# Christmas_Tree_V2.net
KiCad netlist of a schematic drawn in EasyEDA
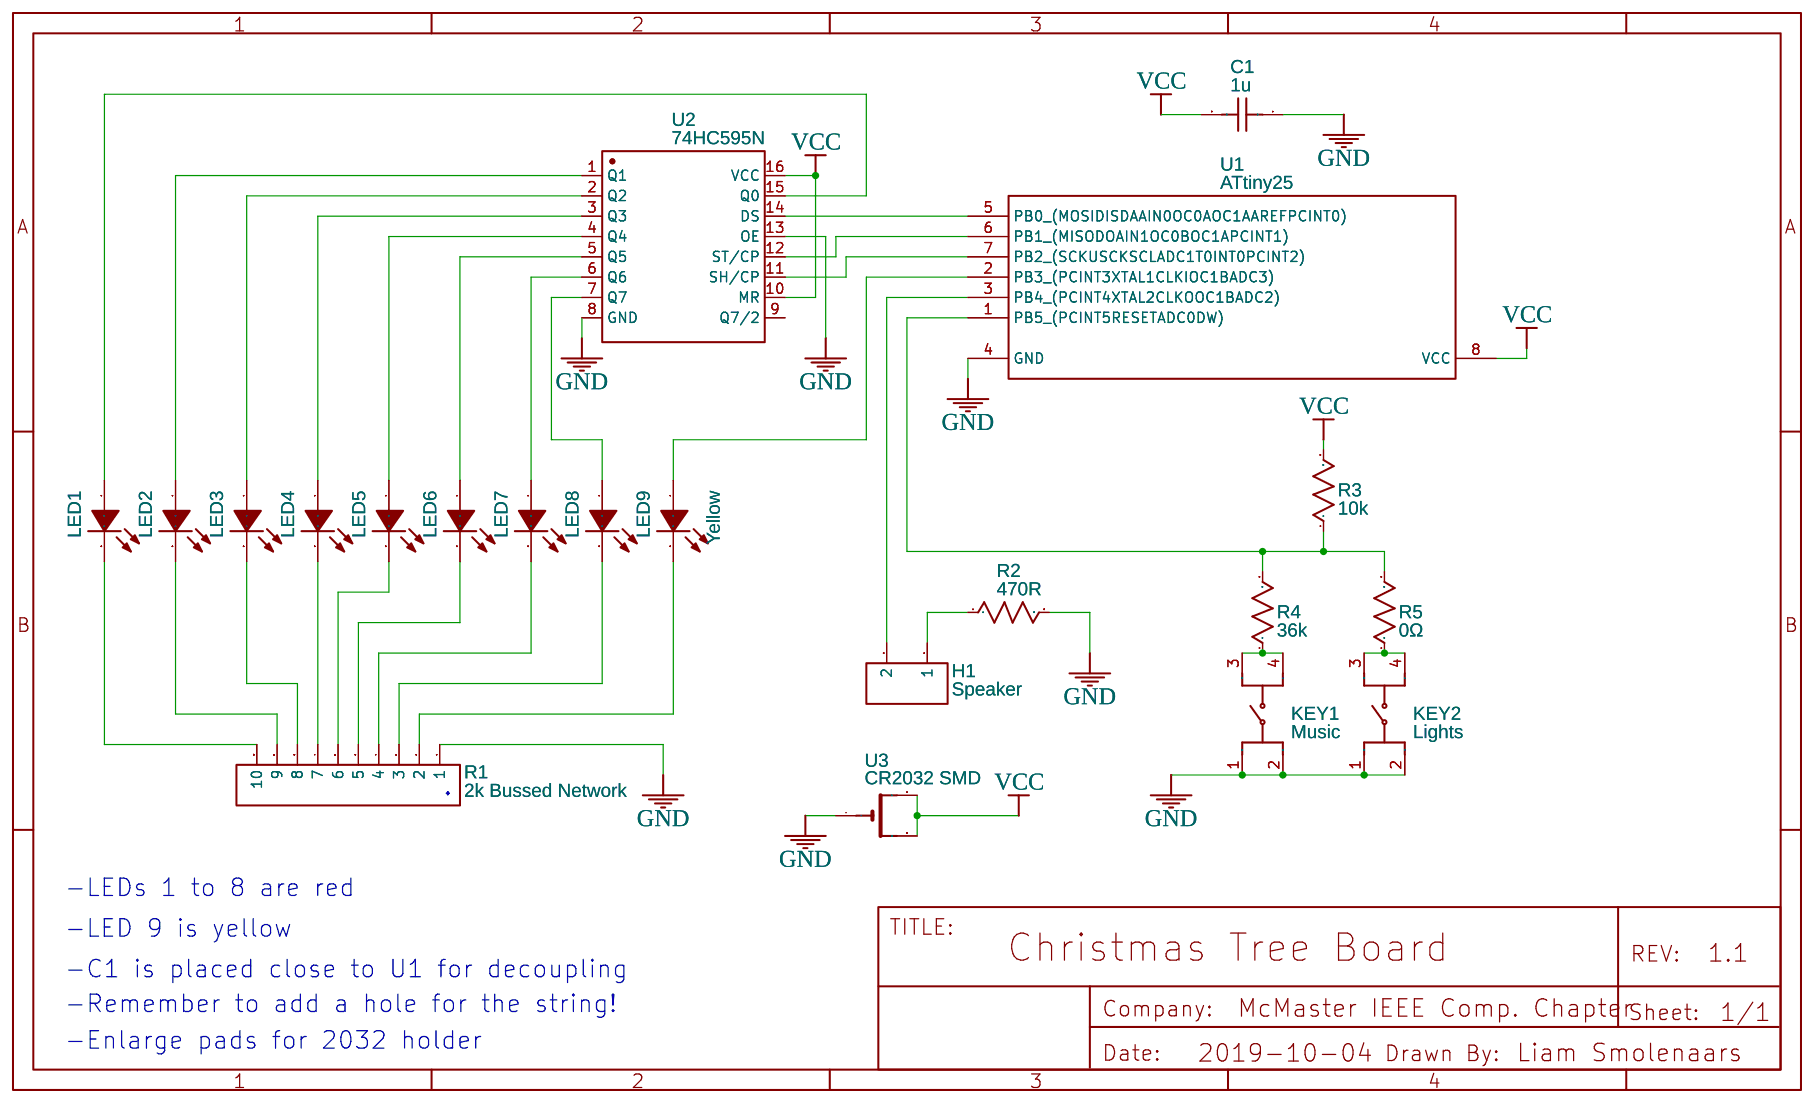
[diagram p0: schematic sheet]

(export (version "E")
  (design (tool "Eeschema 10.0.6"))
  (components
    (comp (ref "C1") (value "1u") (libsource (lib "") (part "Cap_RAD-0.1_US")))
    (comp (ref "H1")
      (value "Speaker")
      (fields (field (name "BOM_Manufacturer Part") "826629-2") (field (name "BOM_Supplier Part") "C86471"))
      (libsource (lib "") (part "Unknown_440_325"))
    )
    (comp (ref "KEY1")
      (value "Music")
      (fields
        (field (name "BOM_Manufacturer Part") "TS-1102-5016")
        (field (name "BOM_Supplier Part") "C111609")
      )
      (libsource (lib "") (part "Unknown_610_345"))
    )
    (comp (ref "KEY2")
      (value "Lights")
      (fields
        (field (name "BOM_Manufacturer Part") "TS-1102-5016")
        (field (name "BOM_Supplier Part") "C111609")
      )
      (libsource (lib "") (part "Unknown_670_345"))
    )
    (comp (ref "LED1")
      (value "204-10SURD/S530-A3")
      (fields (field (name "BOM_Supplier Part") "C99772"))
      (libsource (lib "") (part "Unknown_50_250"))
    )
    (comp (ref "LED2")
      (value "204-10SURD/S530-A3")
      (fields (field (name "BOM_Supplier Part") "C99772"))
      (libsource (lib "") (part "Unknown_85_250"))
    )
    (comp (ref "LED3")
      (value "204-10SURD/S530-A3")
      (fields (field (name "BOM_Supplier Part") "C99772"))
      (libsource (lib "") (part "Unknown_120_250"))
    )
    (comp (ref "LED4")
      (value "204-10SURD/S530-A3")
      (fields (field (name "BOM_Supplier Part") "C99772"))
      (libsource (lib "") (part "Unknown_155_250"))
    )
    (comp (ref "LED5")
      (value "204-10SURD/S530-A3")
      (fields (field (name "BOM_Supplier Part") "C99772"))
      (libsource (lib "") (part "Unknown_190_250"))
    )
    (comp (ref "LED6")
      (value "204-10SURD/S530-A3")
      (fields (field (name "BOM_Supplier Part") "C99772"))
      (libsource (lib "") (part "Unknown_225_250"))
    )
    (comp (ref "LED7")
      (value "204-10SURD/S530-A3")
      (fields (field (name "BOM_Supplier Part") "C99772"))
      (libsource (lib "") (part "Unknown_260_250"))
    )
    (comp (ref "LED8")
      (value "204-10SURD/S530-A3")
      (fields (field (name "BOM_Supplier Part") "C99772"))
      (libsource (lib "") (part "Unknown_295_250"))
    )
    (comp (ref "LED9")
      (value "Yellow")
      (fields
        (field (name "BOM_Manufacturer Part") "204-10SURD/S530-A3")
        (field (name "BOM_Supplier Part") "C99772")
      )
      (libsource (lib "") (part "Unknown_330_250"))
    )
    (comp (ref "R1")
      (value "2k Bussed Network")
      (fields
        (field (name "BOM_Manufacturer Part") "2.54mm 1*10P Straight Female header Gold-plated")
        (field (name "BOM_Supplier Part") "C35445")
      )
      (libsource (lib "") (part "Unknown_160_370"))
    )
    (comp (ref "R2") (value "470R") (libsource (lib "") (part "Res_0805(1/8W)_US_1")))
    (comp (ref "R3") (value "10k") (libsource (lib "") (part "Res_0805(1/8W)_US")))
    (comp (ref "R4") (value "36k") (libsource (lib "") (part "Res_0805(1/8W)_US")))
    (comp (ref "R5") (value "0Ω") (libsource (lib "") (part "Res_0805(1/8W)_US")))
    (comp (ref "U1") (value "ATtiny25") (libsource (lib "") (part "Unknown_600_135")))
    (comp (ref "U2") (value "74HC595N") (libsource (lib "") (part "Unknown_330_115")))
    (comp (ref "U3") (value "CR2032 SMD") (libsource (lib "") (part "Unknown_425_395")))
  )
  (nets
    (net (code "1") (name "GND") (class "Default")
      (node (ref "C1") (pin "1") (pinfunction "1_1") (pintype "unspecified"))
      (node (ref "KEY1") (pin "1") (pinfunction "1_1") (pintype "unspecified"))
      (node (ref "KEY1") (pin "2") (pinfunction "2_2") (pintype "unspecified"))
      (node (ref "KEY2") (pin "1") (pinfunction "1_1") (pintype "unspecified"))
      (node (ref "KEY2") (pin "2") (pinfunction "2_2") (pintype "unspecified"))
      (node (ref "R1") (pin "1") (pinfunction "1_1") (pintype "input"))
      (node (ref "R2") (pin "2") (pinfunction "2_2") (pintype "unspecified"))
      (node (ref "U1") (pin "4") (pinfunction "GND_4") (pintype "passive"))
      (node (ref "U2") (pin "13") (pinfunction "OE_13") (pintype "unspecified"))
      (node (ref "U2") (pin "8") (pinfunction "GND_8") (pintype "unspecified"))
      (node (ref "U3") (pin "-") (pinfunction "-_-") (pintype "unspecified"))
    )
    (net (code "2") (name "Net-(H1-Pad1)") (class "Default")
      (node (ref "H1") (pin "1") (pinfunction "1_1") (pintype "unspecified"))
      (node (ref "R2") (pin "1") (pinfunction "1_1") (pintype "unspecified"))
    )
    (net (code "3") (name "Net-(KEY1-Pad3)") (class "Default")
      (node (ref "KEY1") (pin "3") (pinfunction "3_3") (pintype "unspecified"))
      (node (ref "KEY1") (pin "4") (pinfunction "4_4") (pintype "unspecified"))
      (node (ref "R4") (pin "1") (pinfunction "1_1") (pintype "unspecified"))
    )
    (net (code "4") (name "Net-(KEY2-Pad3)") (class "Default")
      (node (ref "KEY2") (pin "3") (pinfunction "3_3") (pintype "unspecified"))
      (node (ref "KEY2") (pin "4") (pinfunction "4_4") (pintype "unspecified"))
      (node (ref "R5") (pin "1") (pinfunction "1_1") (pintype "unspecified"))
    )
    (net (code "5") (name "Net-(LED1-A)") (class "Default")
      (node (ref "LED1") (pin "1") (pinfunction "A_1") (pintype "unspecified"))
      (node (ref "U2") (pin "15") (pinfunction "Q0_15") (pintype "unspecified"))
    )
    (net (code "6") (name "Net-(LED1-K)") (class "Default")
      (node (ref "LED1") (pin "2") (pinfunction "K_2") (pintype "unspecified"))
      (node (ref "R1") (pin "10") (pinfunction "10_10") (pintype "input"))
    )
    (net (code "7") (name "Net-(LED2-A)") (class "Default")
      (node (ref "LED2") (pin "1") (pinfunction "A_1") (pintype "unspecified"))
      (node (ref "U2") (pin "1") (pinfunction "Q1_1") (pintype "unspecified"))
    )
    (net (code "8") (name "Net-(LED2-K)") (class "Default")
      (node (ref "LED2") (pin "2") (pinfunction "K_2") (pintype "unspecified"))
      (node (ref "R1") (pin "9") (pinfunction "9_9") (pintype "input"))
    )
    (net (code "9") (name "Net-(LED3-A)") (class "Default")
      (node (ref "LED3") (pin "1") (pinfunction "A_1") (pintype "unspecified"))
      (node (ref "U2") (pin "2") (pinfunction "Q2_2") (pintype "unspecified"))
    )
    (net (code "10") (name "Net-(LED3-K)") (class "Default")
      (node (ref "LED3") (pin "2") (pinfunction "K_2") (pintype "unspecified"))
      (node (ref "R1") (pin "8") (pinfunction "8_8") (pintype "input"))
    )
    (net (code "11") (name "Net-(LED4-A)") (class "Default")
      (node (ref "LED4") (pin "1") (pinfunction "A_1") (pintype "unspecified"))
      (node (ref "U2") (pin "3") (pinfunction "Q3_3") (pintype "unspecified"))
    )
    (net (code "12") (name "Net-(LED4-K)") (class "Default")
      (node (ref "LED4") (pin "2") (pinfunction "K_2") (pintype "unspecified"))
      (node (ref "R1") (pin "7") (pinfunction "7_7") (pintype "input"))
    )
    (net (code "13") (name "Net-(LED5-A)") (class "Default")
      (node (ref "LED5") (pin "1") (pinfunction "A_1") (pintype "unspecified"))
      (node (ref "U2") (pin "4") (pinfunction "Q4_4") (pintype "unspecified"))
    )
    (net (code "14") (name "Net-(LED5-K)") (class "Default")
      (node (ref "LED5") (pin "2") (pinfunction "K_2") (pintype "unspecified"))
      (node (ref "R1") (pin "6") (pinfunction "6_6") (pintype "input"))
    )
    (net (code "15") (name "Net-(LED6-A)") (class "Default")
      (node (ref "LED6") (pin "1") (pinfunction "A_1") (pintype "unspecified"))
      (node (ref "U2") (pin "5") (pinfunction "Q5_5") (pintype "unspecified"))
    )
    (net (code "16") (name "Net-(LED6-K)") (class "Default")
      (node (ref "LED6") (pin "2") (pinfunction "K_2") (pintype "unspecified"))
      (node (ref "R1") (pin "5") (pinfunction "5_5") (pintype "input"))
    )
    (net (code "17") (name "Net-(LED7-A)") (class "Default")
      (node (ref "LED7") (pin "1") (pinfunction "A_1") (pintype "unspecified"))
      (node (ref "U2") (pin "6") (pinfunction "Q6_6") (pintype "unspecified"))
    )
    (net (code "18") (name "Net-(LED7-K)") (class "Default")
      (node (ref "LED7") (pin "2") (pinfunction "K_2") (pintype "unspecified"))
      (node (ref "R1") (pin "4") (pinfunction "4_4") (pintype "input"))
    )
    (net (code "19") (name "Net-(LED8-A)") (class "Default")
      (node (ref "LED8") (pin "1") (pinfunction "A_1") (pintype "unspecified"))
      (node (ref "U2") (pin "7") (pinfunction "Q7_7") (pintype "unspecified"))
    )
    (net (code "20") (name "Net-(LED8-K)") (class "Default")
      (node (ref "LED8") (pin "2") (pinfunction "K_2") (pintype "unspecified"))
      (node (ref "R1") (pin "3") (pinfunction "3_3") (pintype "input"))
    )
    (net (code "21") (name "Net-(LED9-A)") (class "Default")
      (node (ref "LED9") (pin "1") (pinfunction "A_1") (pintype "unspecified"))
      (node (ref "U1") (pin "2") (pinfunction "PB3_(PCINT3XTAL1CLKIOC1BADC3)_2") (pintype "bidirectional"))
    )
    (net (code "22") (name "Net-(LED9-K)") (class "Default")
      (node (ref "LED9") (pin "2") (pinfunction "K_2") (pintype "unspecified"))
      (node (ref "R1") (pin "2") (pinfunction "2_2") (pintype "input"))
    )
    (net (code "23") (name "Net-(U1-PB0_(MOSIDISDAAIN0OC0AOC1AAREFPCINT0))") (class "Default")
      (node (ref "U1") (pin "5") (pinfunction "PB0_(MOSIDISDAAIN0OC0AOC1AAREFPCINT0)_5") (pintype "bidirectional"))
      (node (ref "U2") (pin "14") (pinfunction "DS_14") (pintype "unspecified"))
    )
    (net (code "24") (name "Net-(U1-PB1_(MISODOAIN1OC0BOC1APCINT1))") (class "Default")
      (node (ref "U1") (pin "6") (pinfunction "PB1_(MISODOAIN1OC0BOC1APCINT1)_6") (pintype "bidirectional"))
      (node (ref "U2") (pin "12") (pinfunction "ST/CP_12") (pintype "unspecified"))
    )
    (net (code "25") (name "Net-(U1-PB2_(SCKUSCKSCLADC1T0INT0PCINT2))") (class "Default")
      (node (ref "U1") (pin "7") (pinfunction "PB2_(SCKUSCKSCLADC1T0INT0PCINT2)_7") (pintype "bidirectional"))
      (node (ref "U2") (pin "11") (pinfunction "SH/CP_11") (pintype "unspecified"))
    )
    (net (code "26") (name "Net-(U1-PB4_(PCINT4XTAL2CLKOOC1BADC2))") (class "Default")
      (node (ref "H1") (pin "2") (pinfunction "2_2") (pintype "unspecified"))
      (node (ref "U1") (pin "3") (pinfunction "PB4_(PCINT4XTAL2CLKOOC1BADC2)_3") (pintype "bidirectional"))
    )
    (net (code "27") (name "Net-(U1-PB5_(PCINT5RESETADC0DW))") (class "Default")
      (node (ref "R3") (pin "1") (pinfunction "1_1") (pintype "unspecified"))
      (node (ref "R4") (pin "2") (pinfunction "2_2") (pintype "unspecified"))
      (node (ref "R5") (pin "2") (pinfunction "2_2") (pintype "unspecified"))
      (node (ref "U1") (pin "1") (pinfunction "PB5_(PCINT5RESETADC0DW)_1") (pintype "bidirectional"))
    )
    (net (code "28") (name "VCC") (class "Default")
      (node (ref "C1") (pin "2") (pinfunction "2_2") (pintype "unspecified"))
      (node (ref "R3") (pin "2") (pinfunction "2_2") (pintype "unspecified"))
      (node (ref "U1") (pin "8") (pinfunction "VCC_8") (pintype "passive"))
      (node (ref "U2") (pin "10") (pinfunction "MR_10") (pintype "unspecified"))
      (node (ref "U2") (pin "16") (pinfunction "VCC_16") (pintype "unspecified"))
      (node (ref "U3") (pin "+1") (pinfunction "+_+1") (pintype "unspecified"))
      (node (ref "U3") (pin "+2") (pinfunction "+1_+2") (pintype "unspecified"))
    )
    (net (code "29") (name "unconnected-(U2-Q7{slash}2-Pad9)") (class "Default")
      (node (ref "U2") (pin "9") (pinfunction "Q7/2_9") (pintype "unspecified"))
    )
  )
)
